# esp-firework-firing-system-hw1_1.net
KiCad netlist of a schematic drawn in EasyEDA
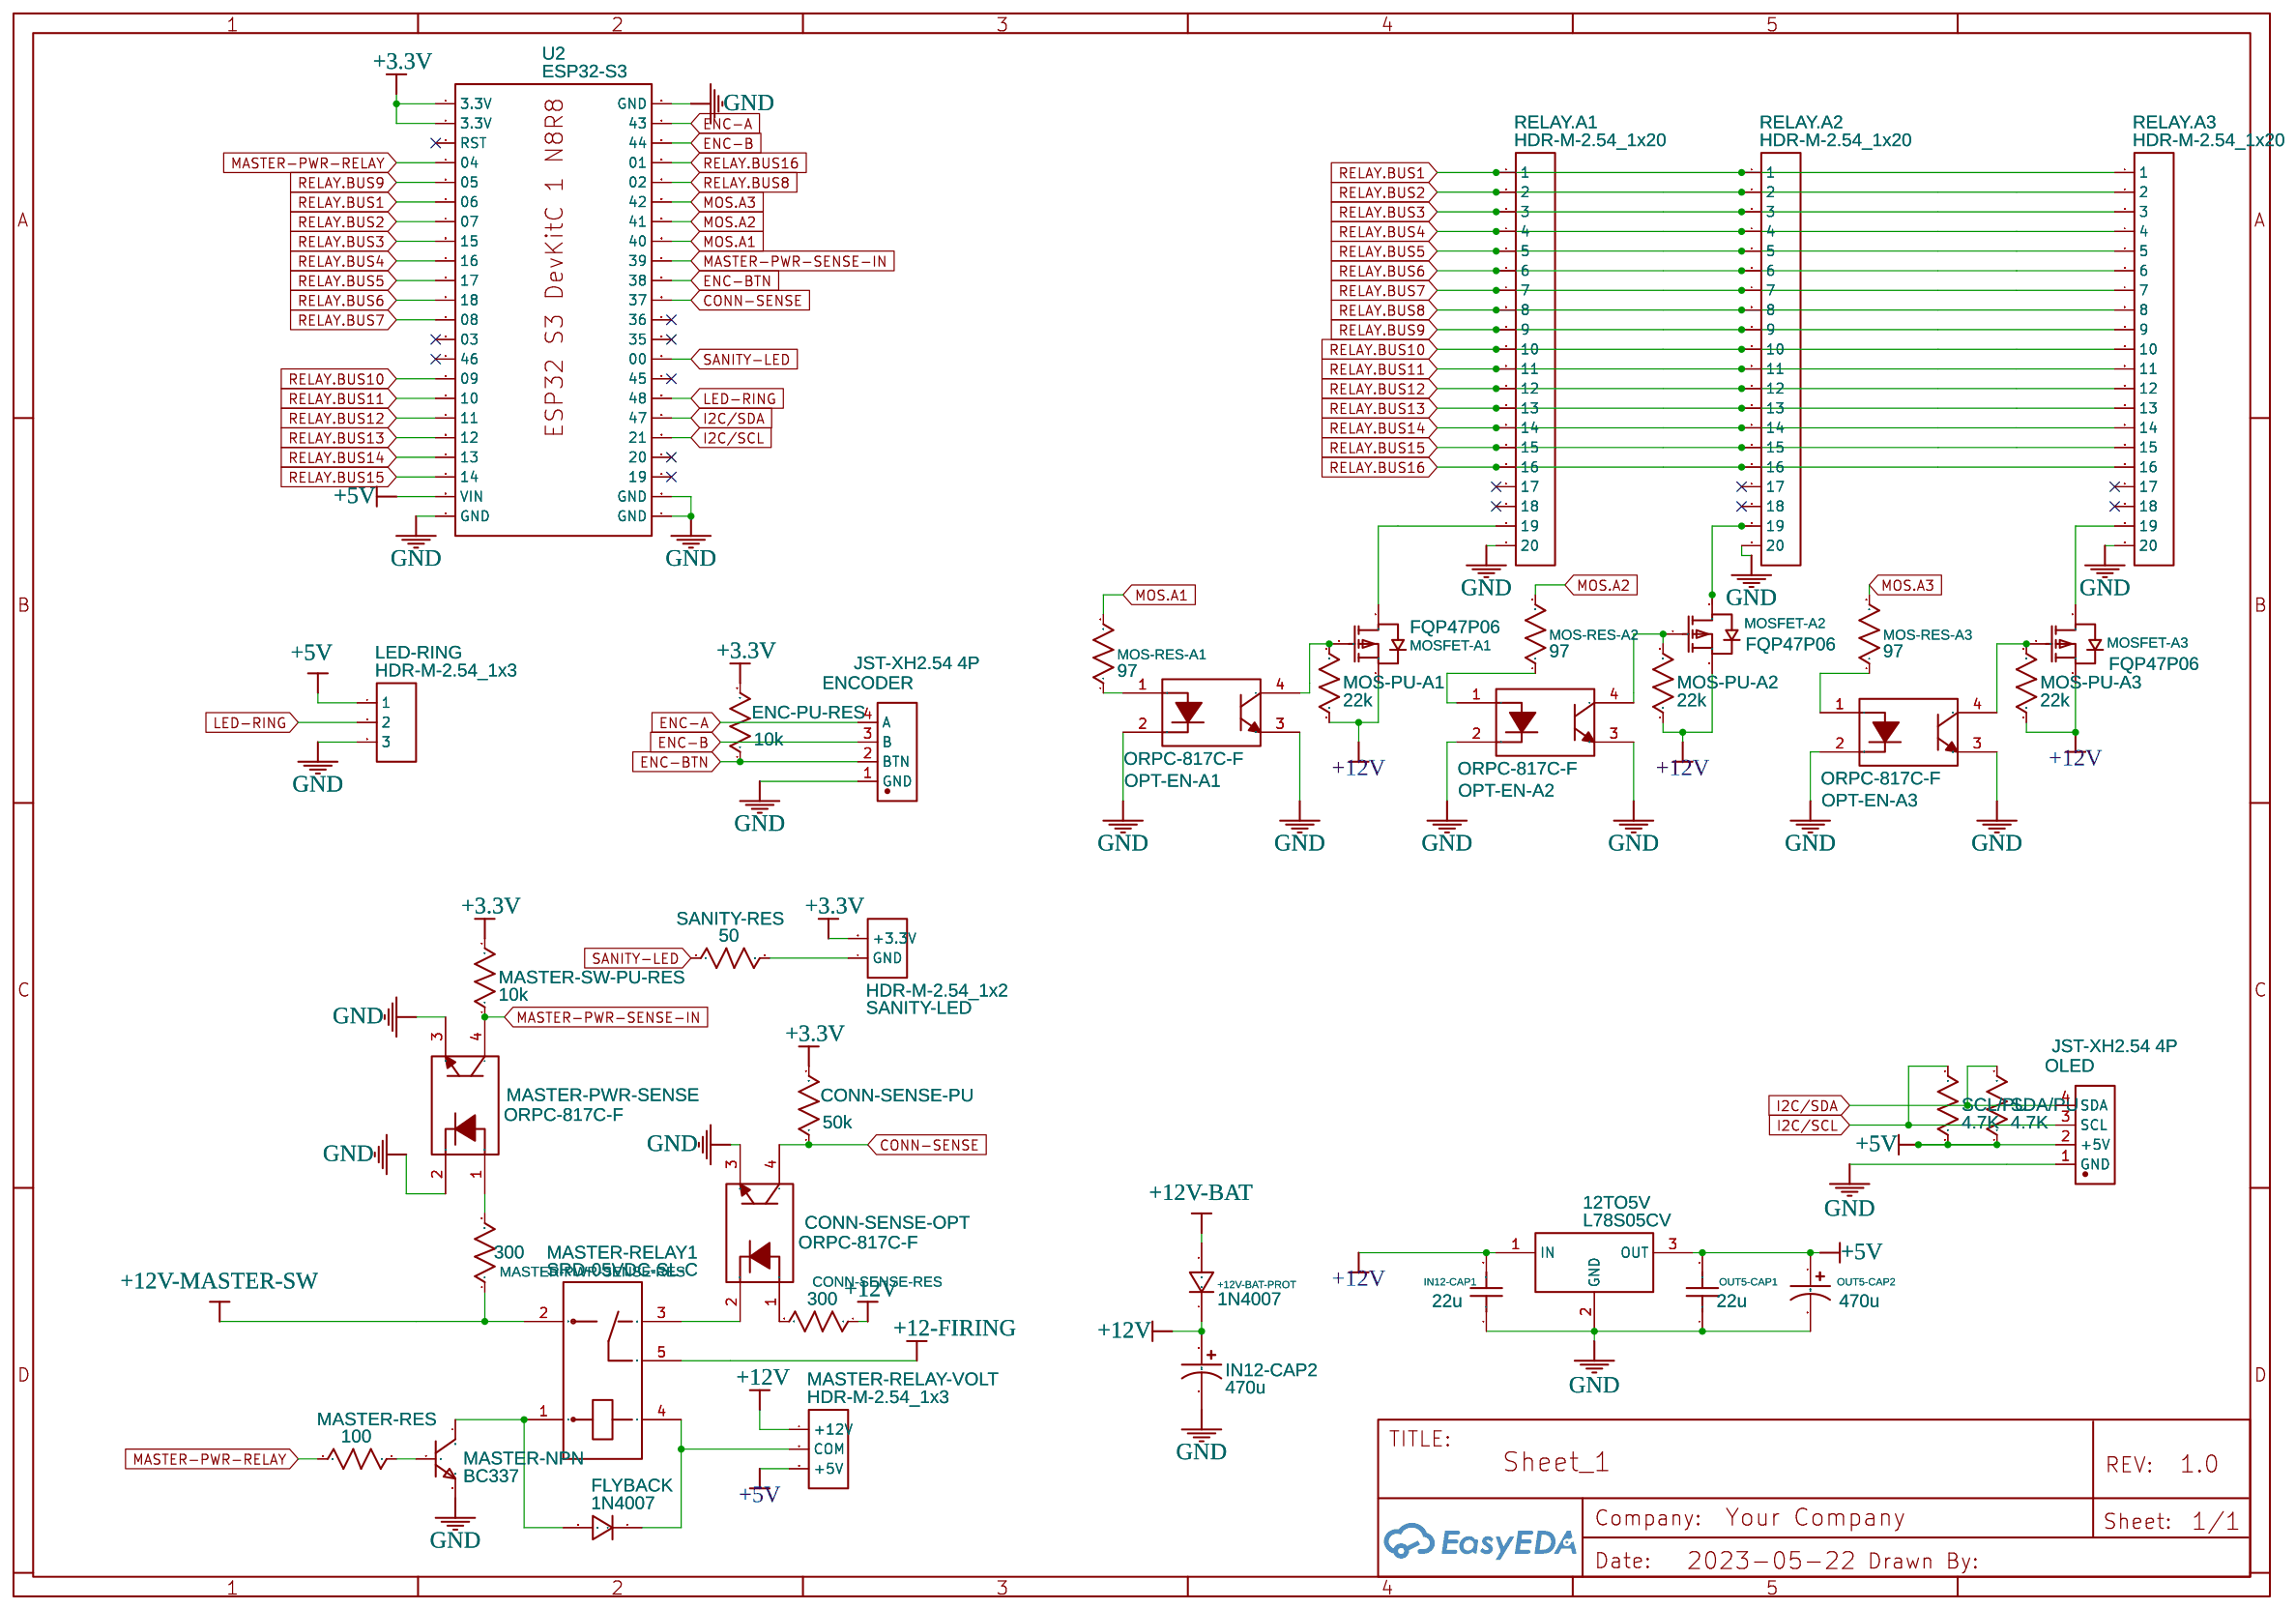
[diagram p0: schematic sheet]

(export (version "E")
  (design (tool "Eeschema 10.0.6"))
  (components
    (comp (ref "+12V-BAT-PROT")
      (value "1N4007")
      (fields (field (name "BOM_Supplier Part") "C106903"))
      (libsource (lib "") (part "1N4007"))
    )
    (comp (ref "12TO5V")
      (value "L78S05CV")
      (fields (field (name "BOM_Supplier Part") "C33043"))
      (libsource (lib "") (part "L78S05CV"))
    )
    (comp (ref "CONN-SENSE-OPT")
      (value "ORPC-817C-F")
      (fields (field (name "BOM_Supplier Part") "C2842770"))
      (libsource (lib "") (part "ORPC-817C-F_1"))
    )
    (comp (ref "CONN-SENSE-PU") (value "50k") (libsource (lib "") (part "R_AXIAL-0.3_US_10")))
    (comp (ref "CONN-SENSE-RES") (value "300") (libsource (lib "") (part "R_AXIAL-0.3_US_9")))
    (comp (ref "ENC-PU-RES") (value "10k") (libsource (lib "") (part "R_AXIAL-0.3_US_6")))
    (comp (ref "ENCODER") (value "JST-XH2.54 4P") (libsource (lib "") (part "JST-XH2.54 4P")))
    (comp (ref "FLYBACK")
      (value "1N4007")
      (fields (field (name "BOM_Supplier Part") "C106903"))
      (libsource (lib "") (part "1N4007_1"))
    )
    (comp (ref "IN12-CAP1") (value "22u") (libsource (lib "") (part "C_RAD-0.1_US_1")))
    (comp (ref "IN12-CAP2") (value "470u") (libsource (lib "") (part "CE_TH_D6.3×F2.5_US_1")))
    (comp (ref "LED-RING")
      (value "HDR-M-2.54_1x3")
      (fields (field (name "BOM_Supplier Part") "C180248"))
      (libsource (lib "") (part "HDR-M-2.54_1x3"))
    )
    (comp (ref "MASTER-NPN") (value "BC337") (libsource (lib "") (part "BC337")))
    (comp (ref "MASTER-PWR-SENSE")
      (value "ORPC-817C-F")
      (fields (field (name "BOM_Supplier Part") "C2842770"))
      (libsource (lib "") (part "ORPC-817C-F"))
    )
    (comp (ref "MASTER-PWR-SENSE-RES") (value "300") (libsource (lib "") (part "R_AXIAL-0.3_US")))
    (comp (ref "MASTER-RELAY-VOLT")
      (value "HDR-M-2.54_1x3")
      (fields (field (name "BOM_Supplier Part") "C180248"))
      (libsource (lib "") (part "HDR-M-2.54_1x3_1"))
    )
    (comp (ref "MASTER-RELAY1")
      (value "SRD-05VDC-SL-C")
      (fields (field (name "BOM_Supplier Part") "C35449"))
      (libsource (lib "") (part "SRD-05VDC-SL-C"))
    )
    (comp (ref "MASTER-RES") (value "100") (libsource (lib "") (part "R_AXIAL-0.3_US_3")))
    (comp (ref "MASTER-SW-PU-RES") (value "10k") (libsource (lib "") (part "R_AXIAL-0.3_US_2")))
    (comp (ref "MOS-PU-A1") (value "22k") (libsource (lib "") (part "R_AXIAL-0.3_US_1")))
    (comp (ref "MOS-PU-A2") (value "22k") (libsource (lib "") (part "R_AXIAL-0.3_US_1")))
    (comp (ref "MOS-PU-A3") (value "22k") (libsource (lib "") (part "R_AXIAL-0.3_US_1")))
    (comp (ref "MOS-RES-A1") (value "97") (libsource (lib "") (part "R_AXIAL-0.3_US_7")))
    (comp (ref "MOS-RES-A2") (value "97") (libsource (lib "") (part "R_AXIAL-0.3_US_7")))
    (comp (ref "MOS-RES-A3") (value "97") (libsource (lib "") (part "R_AXIAL-0.3_US_7")))
    (comp (ref "MOSFET-A1")
      (value "FQP47P06")
      (fields (field (name "BOM_Supplier Part") "C462765"))
      (libsource (lib "") (part "FQP47P06"))
    )
    (comp (ref "MOSFET-A2")
      (value "FQP47P06")
      (fields (field (name "BOM_Supplier Part") "C462765"))
      (libsource (lib "") (part "FQP47P06"))
    )
    (comp (ref "MOSFET-A3")
      (value "FQP47P06")
      (fields (field (name "BOM_Supplier Part") "C462765"))
      (libsource (lib "") (part "FQP47P06"))
    )
    (comp (ref "OLED") (value "JST-XH2.54 4P") (libsource (lib "") (part "JST-XH2.54 4P_1")))
    (comp (ref "OPT-EN-A1")
      (value "ORPC-817C-F")
      (fields (field (name "BOM_Supplier Part") "C2842770"))
      (libsource (lib "") (part "ORPC-817C-F_2"))
    )
    (comp (ref "OPT-EN-A2")
      (value "ORPC-817C-F")
      (fields (field (name "BOM_Supplier Part") "C2842770"))
      (libsource (lib "") (part "ORPC-817C-F_2"))
    )
    (comp (ref "OPT-EN-A3")
      (value "ORPC-817C-F")
      (fields (field (name "BOM_Supplier Part") "C2842770"))
      (libsource (lib "") (part "ORPC-817C-F_2"))
    )
    (comp (ref "OUT5-CAP1") (value "22u") (libsource (lib "") (part "C_RAD-0.1_US")))
    (comp (ref "OUT5-CAP2") (value "470u") (libsource (lib "") (part "CE_TH_D6.3×F2.5_US")))
    (comp (ref "RELAY.A1")
      (value "HDR-M-2.54_1x20")
      (fields (field (name "BOM_Supplier Part") "C50981"))
      (libsource (lib "") (part "HDR-M-2.54_1x20"))
    )
    (comp (ref "RELAY.A2")
      (value "HDR-M-2.54_1x20")
      (fields (field (name "BOM_Supplier Part") "C50981"))
      (libsource (lib "") (part "HDR-M-2.54_1x20"))
    )
    (comp (ref "RELAY.A3")
      (value "HDR-M-2.54_1x20")
      (fields (field (name "BOM_Supplier Part") "C50981"))
      (libsource (lib "") (part "HDR-M-2.54_1x20"))
    )
    (comp (ref "SANITY-LED")
      (value "HDR-M-2.54_1x2")
      (fields (field (name "BOM_Supplier Part") "C124375"))
      (libsource (lib "") (part "HDR-M-2.54_1x2"))
    )
    (comp (ref "SANITY-RES") (value "50") (libsource (lib "") (part "R_AXIAL-0.3_US_5")))
    (comp (ref "SCL/PU") (value "4.7K") (libsource (lib "") (part "R_AXIAL-0.3_US_8")))
    (comp (ref "SDA/PU") (value "4.7K") (libsource (lib "") (part "R_AXIAL-0.3_US_4")))
    (comp (ref "U2") (value "ESP32-S3") (libsource (lib "") (part "ESP32-S3")))
  )
  (nets
    (net (code "1") (name "+3.3V") (class "Default")
      (node (ref "CONN-SENSE-PU") (pin "2") (pinfunction "2_2") (pintype "unspecified"))
      (node (ref "ENC-PU-RES") (pin "2") (pinfunction "2_2") (pintype "unspecified"))
      (node (ref "MASTER-SW-PU-RES") (pin "2") (pinfunction "2_2") (pintype "unspecified"))
      (node (ref "SANITY-LED") (pin "2") (pinfunction "+3.3V_2") (pintype "unspecified"))
      (node (ref "U2") (pin "1") (pinfunction "3.3V_1") (pintype "unspecified"))
      (node (ref "U2") (pin "2") (pinfunction "3.3V_2") (pintype "unspecified"))
    )
    (net (code "2") (name "+5V") (class "Default")
      (node (ref "12TO5V") (pin "3") (pinfunction "OUT_3") (pintype "passive"))
      (node (ref "LED-RING") (pin "1") (pinfunction "1_1") (pintype "input"))
      (node (ref "MASTER-RELAY-VOLT") (pin "3") (pinfunction "+5V_3") (pintype "input"))
      (node (ref "OLED") (pin "2") (pinfunction "+5V_2") (pintype "unspecified"))
      (node (ref "OUT5-CAP1") (pin "2") (pinfunction "2_2") (pintype "unspecified"))
      (node (ref "OUT5-CAP2") (pin "1") (pinfunction "1_1") (pintype "unspecified"))
      (node (ref "SCL/PU") (pin "1") (pinfunction "1_1") (pintype "unspecified"))
      (node (ref "SDA/PU") (pin "1") (pinfunction "1_1") (pintype "unspecified"))
      (node (ref "U2") (pin "21") (pinfunction "VIN_21") (pintype "unspecified"))
    )
    (net (code "3") (name "+12-FIRING") (class "Default")
      (node (ref "MASTER-RELAY1") (pin "5") (pinfunction "5_5") (pintype "input"))
    )
    (net (code "4") (name "+12V") (class "Default")
      (node (ref "+12V-BAT-PROT") (pin "1") (pinfunction "1_1") (pintype "unspecified"))
      (node (ref "12TO5V") (pin "1") (pinfunction "IN_1") (pintype "passive"))
      (node (ref "CONN-SENSE-RES") (pin "1") (pinfunction "1_1") (pintype "unspecified"))
      (node (ref "IN12-CAP1") (pin "2") (pinfunction "2_2") (pintype "unspecified"))
      (node (ref "IN12-CAP2") (pin "1") (pinfunction "1_1") (pintype "unspecified"))
      (node (ref "MASTER-RELAY-VOLT") (pin "1") (pinfunction "+12V_1") (pintype "input"))
      (node (ref "MOS-PU-A1") (pin "1") (pinfunction "1_1") (pintype "unspecified"))
      (node (ref "MOS-PU-A2") (pin "1") (pinfunction "1_1") (pintype "unspecified"))
      (node (ref "MOS-PU-A3") (pin "1") (pinfunction "1_1") (pintype "unspecified"))
      (node (ref "MOSFET-A1") (pin "3") (pinfunction "S_3") (pintype "unspecified"))
      (node (ref "MOSFET-A2") (pin "3") (pinfunction "S_3") (pintype "unspecified"))
      (node (ref "MOSFET-A3") (pin "3") (pinfunction "S_3") (pintype "unspecified"))
    )
    (net (code "5") (name "+12V-BAT") (class "Default")
      (node (ref "+12V-BAT-PROT") (pin "2") (pinfunction "2_2") (pintype "unspecified"))
    )
    (net (code "6") (name "+12V-MASTER-SW") (class "Default")
      (node (ref "MASTER-PWR-SENSE-RES") (pin "1") (pinfunction "1_1") (pintype "unspecified"))
      (node (ref "MASTER-RELAY1") (pin "2") (pinfunction "2_2") (pintype "input"))
    )
    (net (code "7") (name "CONN-SENSE") (class "Default")
      (node (ref "CONN-SENSE-OPT") (pin "4") (pinfunction "4_4") (pintype "unspecified"))
      (node (ref "CONN-SENSE-PU") (pin "1") (pinfunction "1_1") (pintype "unspecified"))
      (node (ref "U2") (pin "33") (pinfunction "37_33") (pintype "unspecified"))
    )
    (net (code "8") (name "ENC-A") (class "Default")
      (node (ref "ENCODER") (pin "4") (pinfunction "A_4") (pintype "unspecified"))
      (node (ref "U2") (pin "24") (pinfunction "43_24") (pintype "unspecified"))
    )
    (net (code "9") (name "ENC-B") (class "Default")
      (node (ref "ENCODER") (pin "3") (pinfunction "B_3") (pintype "unspecified"))
      (node (ref "U2") (pin "25") (pinfunction "44_25") (pintype "unspecified"))
    )
    (net (code "10") (name "ENC-BTN") (class "Default")
      (node (ref "ENC-PU-RES") (pin "1") (pinfunction "1_1") (pintype "unspecified"))
      (node (ref "ENCODER") (pin "2") (pinfunction "BTN_2") (pintype "unspecified"))
      (node (ref "U2") (pin "32") (pinfunction "38_32") (pintype "unspecified"))
    )
    (net (code "11") (name "GND") (class "Default")
      (node (ref "12TO5V") (pin "2") (pinfunction "GND_2") (pintype "passive"))
      (node (ref "CONN-SENSE-OPT") (pin "3") (pinfunction "3_3") (pintype "unspecified"))
      (node (ref "ENCODER") (pin "1") (pinfunction "GND_1") (pintype "unspecified"))
      (node (ref "IN12-CAP1") (pin "1") (pinfunction "1_1") (pintype "unspecified"))
      (node (ref "IN12-CAP2") (pin "2") (pinfunction "2_2") (pintype "unspecified"))
      (node (ref "LED-RING") (pin "3") (pinfunction "3_3") (pintype "input"))
      (node (ref "MASTER-NPN") (pin "3") (pinfunction "E_3") (pintype "unspecified"))
      (node (ref "MASTER-PWR-SENSE") (pin "2") (pinfunction "2_2") (pintype "unspecified"))
      (node (ref "MASTER-PWR-SENSE") (pin "3") (pinfunction "3_3") (pintype "unspecified"))
      (node (ref "OLED") (pin "1") (pinfunction "GND_1") (pintype "unspecified"))
      (node (ref "OPT-EN-A1") (pin "2") (pinfunction "2_2") (pintype "unspecified"))
      (node (ref "OPT-EN-A1") (pin "3") (pinfunction "3_3") (pintype "unspecified"))
      (node (ref "OPT-EN-A2") (pin "2") (pinfunction "2_2") (pintype "unspecified"))
      (node (ref "OPT-EN-A2") (pin "3") (pinfunction "3_3") (pintype "unspecified"))
      (node (ref "OPT-EN-A3") (pin "2") (pinfunction "2_2") (pintype "unspecified"))
      (node (ref "OPT-EN-A3") (pin "3") (pinfunction "3_3") (pintype "unspecified"))
      (node (ref "OUT5-CAP1") (pin "1") (pinfunction "1_1") (pintype "unspecified"))
      (node (ref "OUT5-CAP2") (pin "2") (pinfunction "2_2") (pintype "unspecified"))
      (node (ref "RELAY.A1") (pin "20") (pinfunction "20_20") (pintype "unspecified"))
      (node (ref "RELAY.A2") (pin "20") (pinfunction "20_20") (pintype "unspecified"))
      (node (ref "RELAY.A3") (pin "20") (pinfunction "20_20") (pintype "unspecified"))
      (node (ref "U2") (pin "22") (pinfunction "GND_22") (pintype "unspecified"))
      (node (ref "U2") (pin "23") (pinfunction "GND_23") (pintype "unspecified"))
      (node (ref "U2") (pin "43") (pinfunction "GND_43") (pintype "unspecified"))
      (node (ref "U2") (pin "44") (pinfunction "GND_44") (pintype "unspecified"))
    )
    (net (code "12") (name "I2C{slash}SCL") (class "Default")
      (node (ref "OLED") (pin "3") (pinfunction "SCL_3") (pintype "unspecified"))
      (node (ref "SCL/PU") (pin "2") (pinfunction "2_2") (pintype "unspecified"))
      (node (ref "U2") (pin "40") (pinfunction "21_40") (pintype "unspecified"))
    )
    (net (code "13") (name "I2C{slash}SDA") (class "Default")
      (node (ref "OLED") (pin "4") (pinfunction "SDA_4") (pintype "unspecified"))
      (node (ref "SDA/PU") (pin "2") (pinfunction "2_2") (pintype "unspecified"))
      (node (ref "U2") (pin "39") (pinfunction "47_39") (pintype "unspecified"))
    )
    (net (code "14") (name "LED-RING") (class "Default")
      (node (ref "LED-RING") (pin "2") (pinfunction "2_2") (pintype "input"))
      (node (ref "U2") (pin "38") (pinfunction "48_38") (pintype "unspecified"))
    )
    (net (code "15") (name "MASTER-PWR-RELAY") (class "Default")
      (node (ref "MASTER-RES") (pin "2") (pinfunction "2_2") (pintype "unspecified"))
      (node (ref "U2") (pin "4") (pinfunction "04_4") (pintype "unspecified"))
    )
    (net (code "16") (name "MASTER-PWR-SENSE-IN") (class "Default")
      (node (ref "MASTER-PWR-SENSE") (pin "4") (pinfunction "4_4") (pintype "unspecified"))
      (node (ref "MASTER-SW-PU-RES") (pin "1") (pinfunction "1_1") (pintype "unspecified"))
      (node (ref "U2") (pin "31") (pinfunction "39_31") (pintype "unspecified"))
    )
    (net (code "17") (name "MOS.A1") (class "Default")
      (node (ref "MOS-RES-A1") (pin "2") (pinfunction "2_2") (pintype "unspecified"))
      (node (ref "U2") (pin "30") (pinfunction "40_30") (pintype "unspecified"))
    )
    (net (code "18") (name "MOS.A2") (class "Default")
      (node (ref "MOS-RES-A2") (pin "2") (pinfunction "2_2") (pintype "unspecified"))
      (node (ref "U2") (pin "29") (pinfunction "41_29") (pintype "unspecified"))
    )
    (net (code "19") (name "MOS.A3") (class "Default")
      (node (ref "MOS-RES-A3") (pin "2") (pinfunction "2_2") (pintype "unspecified"))
      (node (ref "U2") (pin "28") (pinfunction "42_28") (pintype "unspecified"))
    )
    (net (code "20") (name "Net-(CONN-SENSE-OPT-Pad1)") (class "Default")
      (node (ref "CONN-SENSE-OPT") (pin "1") (pinfunction "1_1") (pintype "unspecified"))
      (node (ref "CONN-SENSE-RES") (pin "2") (pinfunction "2_2") (pintype "unspecified"))
    )
    (net (code "21") (name "Net-(CONN-SENSE-OPT-Pad2)") (class "Default")
      (node (ref "CONN-SENSE-OPT") (pin "2") (pinfunction "2_2") (pintype "unspecified"))
      (node (ref "MASTER-RELAY1") (pin "3") (pinfunction "3_3") (pintype "input"))
    )
    (net (code "22") (name "Net-(MASTER-NPN-B)") (class "Default")
      (node (ref "MASTER-NPN") (pin "2") (pinfunction "B_2") (pintype "unspecified"))
      (node (ref "MASTER-RES") (pin "1") (pinfunction "1_1") (pintype "unspecified"))
    )
    (net (code "23") (name "Net-(MASTER-NPN-C)") (class "Default")
      (node (ref "FLYBACK") (pin "2") (pinfunction "2_2") (pintype "unspecified"))
      (node (ref "MASTER-NPN") (pin "1") (pinfunction "C_1") (pintype "unspecified"))
      (node (ref "MASTER-RELAY1") (pin "1") (pinfunction "1_1") (pintype "input"))
    )
    (net (code "24") (name "Net-(MASTER-PWR-SENSE-Pad1)") (class "Default")
      (node (ref "MASTER-PWR-SENSE") (pin "1") (pinfunction "1_1") (pintype "unspecified"))
      (node (ref "MASTER-PWR-SENSE-RES") (pin "2") (pinfunction "2_2") (pintype "unspecified"))
    )
    (net (code "25") (name "Net-(MASTER-RELAY-VOLT-COM)") (class "Default")
      (node (ref "FLYBACK") (pin "1") (pinfunction "1_1") (pintype "unspecified"))
      (node (ref "MASTER-RELAY-VOLT") (pin "2") (pinfunction "COM_2") (pintype "input"))
      (node (ref "MASTER-RELAY1") (pin "4") (pinfunction "4_4") (pintype "input"))
    )
    (net (code "26") (name "Net-(MOS-RES-A1-Pad1)") (class "Default")
      (node (ref "MOS-RES-A1") (pin "1") (pinfunction "1_1") (pintype "unspecified"))
      (node (ref "OPT-EN-A1") (pin "1") (pinfunction "1_1") (pintype "unspecified"))
    )
    (net (code "27") (name "Net-(MOS-RES-A2-Pad1)") (class "Default")
      (node (ref "MOS-RES-A2") (pin "1") (pinfunction "1_1") (pintype "unspecified"))
      (node (ref "OPT-EN-A2") (pin "1") (pinfunction "1_1") (pintype "unspecified"))
    )
    (net (code "28") (name "Net-(MOS-RES-A3-Pad1)") (class "Default")
      (node (ref "MOS-RES-A3") (pin "1") (pinfunction "1_1") (pintype "unspecified"))
      (node (ref "OPT-EN-A3") (pin "1") (pinfunction "1_1") (pintype "unspecified"))
    )
    (net (code "29") (name "Net-(MOSFET-A1-D)") (class "Default")
      (node (ref "MOSFET-A1") (pin "2") (pinfunction "D_2") (pintype "unspecified"))
      (node (ref "RELAY.A1") (pin "19") (pinfunction "19_19") (pintype "unspecified"))
    )
    (net (code "30") (name "Net-(MOSFET-A1-G)") (class "Default")
      (node (ref "MOS-PU-A1") (pin "2") (pinfunction "2_2") (pintype "unspecified"))
      (node (ref "MOSFET-A1") (pin "1") (pinfunction "G_1") (pintype "unspecified"))
      (node (ref "OPT-EN-A1") (pin "4") (pinfunction "4_4") (pintype "unspecified"))
    )
    (net (code "31") (name "Net-(MOSFET-A2-D)") (class "Default")
      (node (ref "MOSFET-A2") (pin "2") (pinfunction "D_2") (pintype "unspecified"))
      (node (ref "RELAY.A2") (pin "19") (pinfunction "19_19") (pintype "unspecified"))
    )
    (net (code "32") (name "Net-(MOSFET-A2-G)") (class "Default")
      (node (ref "MOS-PU-A2") (pin "2") (pinfunction "2_2") (pintype "unspecified"))
      (node (ref "MOSFET-A2") (pin "1") (pinfunction "G_1") (pintype "unspecified"))
      (node (ref "OPT-EN-A2") (pin "4") (pinfunction "4_4") (pintype "unspecified"))
    )
    (net (code "33") (name "Net-(MOSFET-A3-D)") (class "Default")
      (node (ref "MOSFET-A3") (pin "2") (pinfunction "D_2") (pintype "unspecified"))
      (node (ref "RELAY.A3") (pin "19") (pinfunction "19_19") (pintype "unspecified"))
    )
    (net (code "34") (name "Net-(MOSFET-A3-G)") (class "Default")
      (node (ref "MOS-PU-A3") (pin "2") (pinfunction "2_2") (pintype "unspecified"))
      (node (ref "MOSFET-A3") (pin "1") (pinfunction "G_1") (pintype "unspecified"))
      (node (ref "OPT-EN-A3") (pin "4") (pinfunction "4_4") (pintype "unspecified"))
    )
    (net (code "35") (name "Net-(SANITY-LED-GND)") (class "Default")
      (node (ref "SANITY-LED") (pin "1") (pinfunction "GND_1") (pintype "unspecified"))
      (node (ref "SANITY-RES") (pin "2") (pinfunction "2_2") (pintype "unspecified"))
    )
    (net (code "36") (name "RELAY.BUS1") (class "Default")
      (node (ref "RELAY.A1") (pin "1") (pinfunction "1_1") (pintype "unspecified"))
      (node (ref "RELAY.A2") (pin "1") (pinfunction "1_1") (pintype "unspecified"))
      (node (ref "RELAY.A3") (pin "1") (pinfunction "1_1") (pintype "unspecified"))
      (node (ref "U2") (pin "6") (pinfunction "06_6") (pintype "unspecified"))
    )
    (net (code "37") (name "RELAY.BUS2") (class "Default")
      (node (ref "RELAY.A1") (pin "2") (pinfunction "2_2") (pintype "unspecified"))
      (node (ref "RELAY.A2") (pin "2") (pinfunction "2_2") (pintype "unspecified"))
      (node (ref "RELAY.A3") (pin "2") (pinfunction "2_2") (pintype "unspecified"))
      (node (ref "U2") (pin "7") (pinfunction "07_7") (pintype "unspecified"))
    )
    (net (code "38") (name "RELAY.BUS3") (class "Default")
      (node (ref "RELAY.A1") (pin "3") (pinfunction "3_3") (pintype "unspecified"))
      (node (ref "RELAY.A2") (pin "3") (pinfunction "3_3") (pintype "unspecified"))
      (node (ref "RELAY.A3") (pin "3") (pinfunction "3_3") (pintype "unspecified"))
      (node (ref "U2") (pin "8") (pinfunction "15_8") (pintype "unspecified"))
    )
    (net (code "39") (name "RELAY.BUS4") (class "Default")
      (node (ref "RELAY.A1") (pin "4") (pinfunction "4_4") (pintype "unspecified"))
      (node (ref "RELAY.A2") (pin "4") (pinfunction "4_4") (pintype "unspecified"))
      (node (ref "RELAY.A3") (pin "4") (pinfunction "4_4") (pintype "unspecified"))
      (node (ref "U2") (pin "9") (pinfunction "16_9") (pintype "unspecified"))
    )
    (net (code "40") (name "RELAY.BUS5") (class "Default")
      (node (ref "RELAY.A1") (pin "5") (pinfunction "5_5") (pintype "unspecified"))
      (node (ref "RELAY.A2") (pin "5") (pinfunction "5_5") (pintype "unspecified"))
      (node (ref "RELAY.A3") (pin "5") (pinfunction "5_5") (pintype "unspecified"))
      (node (ref "U2") (pin "10") (pinfunction "17_10") (pintype "unspecified"))
    )
    (net (code "41") (name "RELAY.BUS6") (class "Default")
      (node (ref "RELAY.A1") (pin "6") (pinfunction "6_6") (pintype "unspecified"))
      (node (ref "RELAY.A2") (pin "6") (pinfunction "6_6") (pintype "unspecified"))
      (node (ref "RELAY.A3") (pin "6") (pinfunction "6_6") (pintype "unspecified"))
      (node (ref "U2") (pin "11") (pinfunction "18_11") (pintype "unspecified"))
    )
    (net (code "42") (name "RELAY.BUS7") (class "Default")
      (node (ref "RELAY.A1") (pin "7") (pinfunction "7_7") (pintype "unspecified"))
      (node (ref "RELAY.A2") (pin "7") (pinfunction "7_7") (pintype "unspecified"))
      (node (ref "RELAY.A3") (pin "7") (pinfunction "7_7") (pintype "unspecified"))
      (node (ref "U2") (pin "12") (pinfunction "08_12") (pintype "unspecified"))
    )
    (net (code "43") (name "RELAY.BUS8") (class "Default")
      (node (ref "RELAY.A1") (pin "8") (pinfunction "8_8") (pintype "unspecified"))
      (node (ref "RELAY.A2") (pin "8") (pinfunction "8_8") (pintype "unspecified"))
      (node (ref "RELAY.A3") (pin "8") (pinfunction "8_8") (pintype "unspecified"))
      (node (ref "U2") (pin "27") (pinfunction "02_27") (pintype "unspecified"))
    )
    (net (code "44") (name "RELAY.BUS9") (class "Default")
      (node (ref "RELAY.A1") (pin "9") (pinfunction "9_9") (pintype "unspecified"))
      (node (ref "RELAY.A2") (pin "9") (pinfunction "9_9") (pintype "unspecified"))
      (node (ref "RELAY.A3") (pin "9") (pinfunction "9_9") (pintype "unspecified"))
      (node (ref "U2") (pin "5") (pinfunction "05_5") (pintype "unspecified"))
    )
    (net (code "45") (name "RELAY.BUS10") (class "Default")
      (node (ref "RELAY.A1") (pin "10") (pinfunction "10_10") (pintype "unspecified"))
      (node (ref "RELAY.A2") (pin "10") (pinfunction "10_10") (pintype "unspecified"))
      (node (ref "RELAY.A3") (pin "10") (pinfunction "10_10") (pintype "unspecified"))
      (node (ref "U2") (pin "15") (pinfunction "09_15") (pintype "unspecified"))
    )
    (net (code "46") (name "RELAY.BUS11") (class "Default")
      (node (ref "RELAY.A1") (pin "11") (pinfunction "11_11") (pintype "unspecified"))
      (node (ref "RELAY.A2") (pin "11") (pinfunction "11_11") (pintype "unspecified"))
      (node (ref "RELAY.A3") (pin "11") (pinfunction "11_11") (pintype "unspecified"))
      (node (ref "U2") (pin "16") (pinfunction "10_16") (pintype "unspecified"))
    )
    (net (code "47") (name "RELAY.BUS12") (class "Default")
      (node (ref "RELAY.A1") (pin "12") (pinfunction "12_12") (pintype "unspecified"))
      (node (ref "RELAY.A2") (pin "12") (pinfunction "12_12") (pintype "unspecified"))
      (node (ref "RELAY.A3") (pin "12") (pinfunction "12_12") (pintype "unspecified"))
      (node (ref "U2") (pin "17") (pinfunction "11_17") (pintype "unspecified"))
    )
    (net (code "48") (name "RELAY.BUS13") (class "Default")
      (node (ref "RELAY.A1") (pin "13") (pinfunction "13_13") (pintype "unspecified"))
      (node (ref "RELAY.A2") (pin "13") (pinfunction "13_13") (pintype "unspecified"))
      (node (ref "RELAY.A3") (pin "13") (pinfunction "13_13") (pintype "unspecified"))
      (node (ref "U2") (pin "18") (pinfunction "12_18") (pintype "unspecified"))
    )
    (net (code "49") (name "RELAY.BUS14") (class "Default")
      (node (ref "RELAY.A1") (pin "14") (pinfunction "14_14") (pintype "unspecified"))
      (node (ref "RELAY.A2") (pin "14") (pinfunction "14_14") (pintype "unspecified"))
      (node (ref "RELAY.A3") (pin "14") (pinfunction "14_14") (pintype "unspecified"))
      (node (ref "U2") (pin "19") (pinfunction "13_19") (pintype "unspecified"))
    )
    (net (code "50") (name "RELAY.BUS15") (class "Default")
      (node (ref "RELAY.A1") (pin "15") (pinfunction "15_15") (pintype "unspecified"))
      (node (ref "RELAY.A2") (pin "15") (pinfunction "15_15") (pintype "unspecified"))
      (node (ref "RELAY.A3") (pin "15") (pinfunction "15_15") (pintype "unspecified"))
      (node (ref "U2") (pin "20") (pinfunction "14_20") (pintype "unspecified"))
    )
    (net (code "51") (name "RELAY.BUS16") (class "Default")
      (node (ref "RELAY.A1") (pin "16") (pinfunction "16_16") (pintype "unspecified"))
      (node (ref "RELAY.A2") (pin "16") (pinfunction "16_16") (pintype "unspecified"))
      (node (ref "RELAY.A3") (pin "16") (pinfunction "16_16") (pintype "unspecified"))
      (node (ref "U2") (pin "26") (pinfunction "01_26") (pintype "unspecified"))
    )
    (net (code "52") (name "SANITY-LED") (class "Default")
      (node (ref "SANITY-RES") (pin "1") (pinfunction "1_1") (pintype "unspecified"))
      (node (ref "U2") (pin "36") (pinfunction "00_36") (pintype "unspecified"))
    )
    (net (code "53") (name "unconnected-(RELAY.A1-Pad17)") (class "Default")
      (node (ref "RELAY.A1") (pin "17") (pinfunction "17_17") (pintype "unspecified+no_connect"))
    )
    (net (code "54") (name "unconnected-(RELAY.A1-Pad18)") (class "Default")
      (node (ref "RELAY.A1") (pin "18") (pinfunction "18_18") (pintype "unspecified+no_connect"))
    )
    (net (code "55") (name "unconnected-(RELAY.A2-Pad17)") (class "Default")
      (node (ref "RELAY.A2") (pin "17") (pinfunction "17_17") (pintype "unspecified+no_connect"))
    )
    (net (code "56") (name "unconnected-(RELAY.A2-Pad18)") (class "Default")
      (node (ref "RELAY.A2") (pin "18") (pinfunction "18_18") (pintype "unspecified+no_connect"))
    )
    (net (code "57") (name "unconnected-(RELAY.A3-Pad17)") (class "Default")
      (node (ref "RELAY.A3") (pin "17") (pinfunction "17_17") (pintype "unspecified+no_connect"))
    )
    (net (code "58") (name "unconnected-(RELAY.A3-Pad18)") (class "Default")
      (node (ref "RELAY.A3") (pin "18") (pinfunction "18_18") (pintype "unspecified+no_connect"))
    )
    (net (code "59") (name "unconnected-(U2-03-Pad13)") (class "Default")
      (node (ref "U2") (pin "13") (pinfunction "03_13") (pintype "unspecified+no_connect"))
    )
    (net (code "60") (name "unconnected-(U2-19-Pad42)") (class "Default")
      (node (ref "U2") (pin "42") (pinfunction "19_42") (pintype "unspecified+no_connect"))
    )
    (net (code "61") (name "unconnected-(U2-20-Pad41)") (class "Default")
      (node (ref "U2") (pin "41") (pinfunction "20_41") (pintype "unspecified+no_connect"))
    )
    (net (code "62") (name "unconnected-(U2-36-Pad34)") (class "Default")
      (node (ref "U2") (pin "34") (pinfunction "36_34") (pintype "unspecified+no_connect"))
    )
    (net (code "63") (name "unconnected-(U2-45-Pad37)") (class "Default")
      (node (ref "U2") (pin "37") (pinfunction "45_37") (pintype "unspecified+no_connect"))
    )
    (net (code "64") (name "unconnected-(U2-46-Pad14)") (class "Default")
      (node (ref "U2") (pin "14") (pinfunction "46_14") (pintype "unspecified+no_connect"))
    )
    (net (code "65") (name "unconnected-(U2-Pad35)") (class "Default")
      (node (ref "U2") (pin "35") (pinfunction "35_35") (pintype "unspecified+no_connect"))
    )
    (net (code "66") (name "unconnected-(U2-RST-Pad3)") (class "Default")
      (node (ref "U2") (pin "3") (pinfunction "RST_3") (pintype "unspecified+no_connect"))
    )
  )
)
